# board1.net
KiCad netlist of a schematic drawn in EAGLE
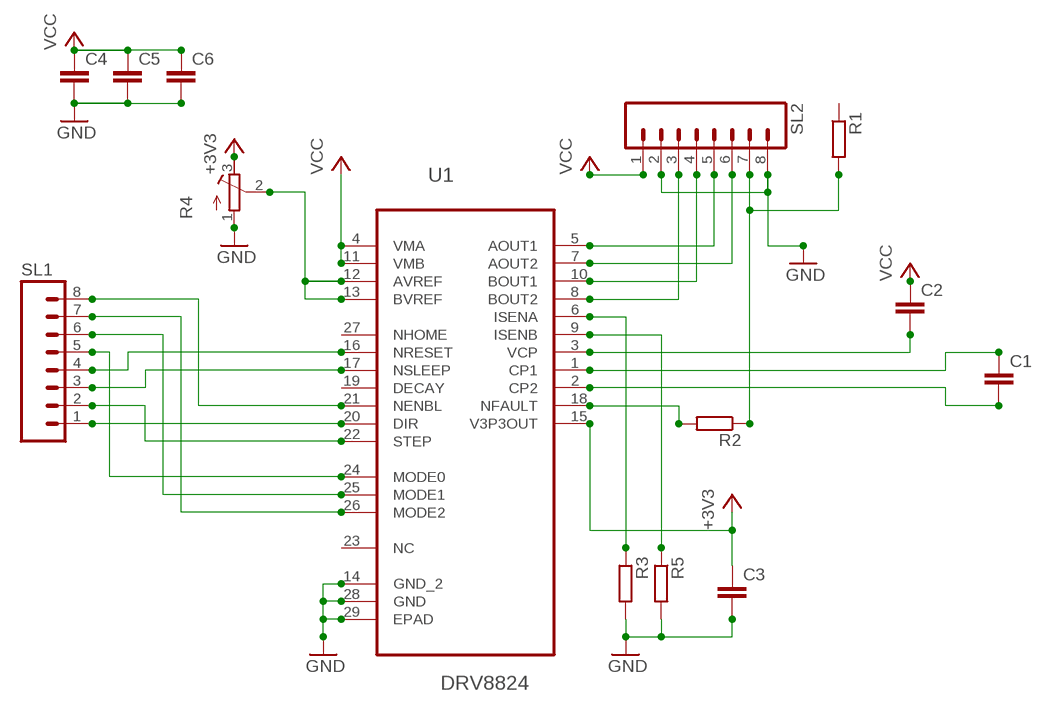
[diagram p0: schematic, sheet 1]

(export (version "E")
  (design (tool "Eeschema 10.0.6"))
  (components
    (comp (ref "C1")
      (value "C-EU025-030X050")
      (footprint "eagle-import:C025-030X050")
      (libsource (lib "eagle-import") (part "C-EU025-030X050"))
    )
    (comp (ref "C2")
      (value "C-EU025-030X050")
      (footprint "eagle-import:C025-030X050")
      (libsource (lib "eagle-import") (part "C-EU025-030X050"))
    )
    (comp (ref "C3")
      (value "C-EU025-030X050")
      (footprint "eagle-import:C025-030X050")
      (libsource (lib "eagle-import") (part "C-EU025-030X050"))
    )
    (comp (ref "C4")
      (value "C-EU025-030X050")
      (footprint "eagle-import:C025-030X050")
      (libsource (lib "eagle-import") (part "C-EU025-030X050"))
    )
    (comp (ref "C5")
      (value "C-EU025-030X050")
      (footprint "eagle-import:C025-030X050")
      (libsource (lib "eagle-import") (part "C-EU025-030X050"))
    )
    (comp (ref "C6")
      (value "C-EU025-030X050")
      (footprint "eagle-import:C025-030X050")
      (libsource (lib "eagle-import") (part "C-EU025-030X050"))
    )
    (comp (ref "R1")
      (value "R-EU_0207/7")
      (footprint "eagle-import:0207_7")
      (libsource (lib "eagle-import") (part "R-EU_0207/7"))
    )
    (comp (ref "R2")
      (value "R-EU_0207/7")
      (footprint "eagle-import:0207_7")
      (libsource (lib "eagle-import") (part "R-EU_0207/7"))
    )
    (comp (ref "R3")
      (value "R-EU_0207/7")
      (footprint "eagle-import:0207_7")
      (libsource (lib "eagle-import") (part "R-EU_0207/7"))
    )
    (comp (ref "R4")
      (value "R-TRIMM64Y")
      (footprint "eagle-import:RTRIM64Y")
      (libsource (lib "eagle-import") (part "R-TRIMM64Y"))
    )
    (comp (ref "R5")
      (value "R-EU_0207/7")
      (footprint "eagle-import:0207_7")
      (libsource (lib "eagle-import") (part "R-EU_0207/7"))
    )
    (comp (ref "SL1")
      (value "M08")
      (footprint "eagle-import:08P")
      (libsource (lib "eagle-import") (part "M08"))
    )
    (comp (ref "SL2")
      (value "M08")
      (footprint "eagle-import:08P")
      (libsource (lib "eagle-import") (part "M08"))
    )
    (comp (ref "U1")
      (value "DRV8824")
      (footprint "eagle-import:SOP65P640X120-29N")
      (fields (field (name "MPN") "DRV8824PWPR"))
      (libsource (lib "eagle-import") (part "DRV8824PWPR"))
    )
  )
  (nets
    (net (code "1") (name "+3V3") (class "Default")
      (node (ref "C3") (pin "1") (pinfunction "1_1") (pintype "passive"))
      (node (ref "R4") (pin "3") (pinfunction "A_3") (pintype "passive"))
      (node (ref "U1") (pin "15") (pinfunction "V3P3OUT_15") (pintype "output"))
    )
    (net (code "2") (name "GND") (class "Default")
      (node (ref "C3") (pin "2") (pinfunction "2_2") (pintype "passive"))
      (node (ref "C4") (pin "2") (pinfunction "2_2") (pintype "passive"))
      (node (ref "C5") (pin "2") (pinfunction "2_2") (pintype "passive"))
      (node (ref "C6") (pin "2") (pinfunction "2_2") (pintype "passive"))
      (node (ref "R3") (pin "2") (pinfunction "2_2") (pintype "passive"))
      (node (ref "R4") (pin "1") (pinfunction "E_1") (pintype "passive"))
      (node (ref "R5") (pin "2") (pinfunction "2_2") (pintype "passive"))
      (node (ref "SL2") (pin "2") (pinfunction "2_2") (pintype "passive"))
      (node (ref "SL2") (pin "8") (pinfunction "8_8") (pintype "passive"))
      (node (ref "U1") (pin "14") (pinfunction "GND_2_14") (pintype "passive"))
      (node (ref "U1") (pin "28") (pinfunction "GND_28") (pintype "passive"))
      (node (ref "U1") (pin "29") (pinfunction "EPAD_29") (pintype "passive"))
    )
    (net (code "3") (name "Net-(R1-Pad2)") (class "Default")
      (node (ref "R1") (pin "2") (pinfunction "2_2") (pintype "passive"))
      (node (ref "R2") (pin "1") (pinfunction "1_1") (pintype "passive"))
      (node (ref "SL2") (pin "7") (pinfunction "7_7") (pintype "passive"))
    )
    (net (code "4") (name "Net-(R4-S)") (class "Default")
      (node (ref "R4") (pin "2") (pinfunction "S_2") (pintype "passive"))
      (node (ref "U1") (pin "12") (pinfunction "AVREF_12") (pintype "input"))
      (node (ref "U1") (pin "13") (pinfunction "BVREF_13") (pintype "input"))
    )
    (net (code "5") (name "Net-(U1-AOUT1)") (class "Default")
      (node (ref "SL2") (pin "5") (pinfunction "5_5") (pintype "passive"))
      (node (ref "U1") (pin "5") (pinfunction "AOUT1_5") (pintype "output"))
    )
    (net (code "6") (name "Net-(U1-AOUT2)") (class "Default")
      (node (ref "SL2") (pin "6") (pinfunction "6_6") (pintype "passive"))
      (node (ref "U1") (pin "7") (pinfunction "AOUT2_7") (pintype "output"))
    )
    (net (code "7") (name "Net-(U1-BOUT1)") (class "Default")
      (node (ref "SL2") (pin "4") (pinfunction "4_4") (pintype "passive"))
      (node (ref "U1") (pin "10") (pinfunction "BOUT1_10") (pintype "output"))
    )
    (net (code "8") (name "Net-(U1-BOUT2)") (class "Default")
      (node (ref "SL2") (pin "3") (pinfunction "3_3") (pintype "passive"))
      (node (ref "U1") (pin "8") (pinfunction "BOUT2_8") (pintype "output"))
    )
    (net (code "9") (name "Net-(U1-CP1)") (class "Default")
      (node (ref "C1") (pin "1") (pinfunction "1_1") (pintype "passive"))
      (node (ref "U1") (pin "1") (pinfunction "CP1_1") (pintype "bidirectional"))
    )
    (net (code "10") (name "Net-(U1-CP2)") (class "Default")
      (node (ref "C1") (pin "2") (pinfunction "2_2") (pintype "passive"))
      (node (ref "U1") (pin "2") (pinfunction "CP2_2") (pintype "bidirectional"))
    )
    (net (code "11") (name "Net-(U1-DIR)") (class "Default")
      (node (ref "SL1") (pin "1") (pinfunction "1_1") (pintype "passive"))
      (node (ref "U1") (pin "20") (pinfunction "DIR_20") (pintype "input"))
    )
    (net (code "12") (name "Net-(U1-ISENA)") (class "Default")
      (node (ref "R3") (pin "1") (pinfunction "1_1") (pintype "passive"))
      (node (ref "U1") (pin "6") (pinfunction "ISENA_6") (pintype "bidirectional"))
    )
    (net (code "13") (name "Net-(U1-ISENB)") (class "Default")
      (node (ref "R5") (pin "1") (pinfunction "1_1") (pintype "passive"))
      (node (ref "U1") (pin "9") (pinfunction "ISENB_9") (pintype "bidirectional"))
    )
    (net (code "14") (name "Net-(U1-MODE0)") (class "Default")
      (node (ref "SL1") (pin "5") (pinfunction "5_5") (pintype "passive"))
      (node (ref "U1") (pin "24") (pinfunction "MODE0_24") (pintype "input"))
    )
    (net (code "15") (name "Net-(U1-MODE1)") (class "Default")
      (node (ref "SL1") (pin "6") (pinfunction "6_6") (pintype "passive"))
      (node (ref "U1") (pin "25") (pinfunction "MODE1_25") (pintype "input"))
    )
    (net (code "16") (name "Net-(U1-MODE2)") (class "Default")
      (node (ref "SL1") (pin "7") (pinfunction "7_7") (pintype "passive"))
      (node (ref "U1") (pin "26") (pinfunction "MODE2_26") (pintype "input"))
    )
    (net (code "17") (name "Net-(U1-NENBL)") (class "Default")
      (node (ref "SL1") (pin "8") (pinfunction "8_8") (pintype "passive"))
      (node (ref "U1") (pin "21") (pinfunction "NENBL_21") (pintype "input"))
    )
    (net (code "18") (name "Net-(U1-NFAULT)") (class "Default")
      (node (ref "R2") (pin "2") (pinfunction "2_2") (pintype "passive"))
      (node (ref "U1") (pin "18") (pinfunction "NFAULT_18") (pintype "output"))
    )
    (net (code "19") (name "Net-(U1-NRESET)") (class "Default")
      (node (ref "SL1") (pin "4") (pinfunction "4_4") (pintype "passive"))
      (node (ref "U1") (pin "16") (pinfunction "NRESET_16") (pintype "input"))
    )
    (net (code "20") (name "Net-(U1-NSLEEP)") (class "Default")
      (node (ref "SL1") (pin "3") (pinfunction "3_3") (pintype "passive"))
      (node (ref "U1") (pin "17") (pinfunction "NSLEEP_17") (pintype "input"))
    )
    (net (code "21") (name "Net-(U1-STEP)") (class "Default")
      (node (ref "SL1") (pin "2") (pinfunction "2_2") (pintype "passive"))
      (node (ref "U1") (pin "22") (pinfunction "STEP_22") (pintype "input"))
    )
    (net (code "22") (name "Net-(U1-VCP)") (class "Default")
      (node (ref "C2") (pin "2") (pinfunction "2_2") (pintype "passive"))
      (node (ref "U1") (pin "3") (pinfunction "VCP_3") (pintype "bidirectional"))
    )
    (net (code "23") (name "VCC") (class "Default")
      (node (ref "C2") (pin "1") (pinfunction "1_1") (pintype "passive"))
      (node (ref "C4") (pin "1") (pinfunction "1_1") (pintype "passive"))
      (node (ref "C5") (pin "1") (pinfunction "1_1") (pintype "passive"))
      (node (ref "C6") (pin "1") (pinfunction "1_1") (pintype "passive"))
      (node (ref "SL2") (pin "1") (pinfunction "1_1") (pintype "passive"))
      (node (ref "U1") (pin "11") (pinfunction "VMB_11") (pintype "power_in"))
      (node (ref "U1") (pin "4") (pinfunction "VMA_4") (pintype "power_in"))
    )
    (net (code "24") (name "unconnected-(R1-Pad1)") (class "Default")
      (node (ref "R1") (pin "1") (pinfunction "1_1") (pintype "passive"))
    )
    (net (code "25") (name "unconnected-(U1-DECAY-Pad19)") (class "Default")
      (node (ref "U1") (pin "19") (pinfunction "DECAY_19") (pintype "input"))
    )
    (net (code "26") (name "unconnected-(U1-NC-Pad23)") (class "Default")
      (node (ref "U1") (pin "23") (pinfunction "NC_23") (pintype "no_connect"))
    )
    (net (code "27") (name "unconnected-(U1-NHOME-Pad27)") (class "Default")
      (node (ref "U1") (pin "27") (pinfunction "NHOME_27") (pintype "input"))
    )
  )
)
